# smps_v_1_1.net
KiCad netlist of a schematic drawn in EAGLE
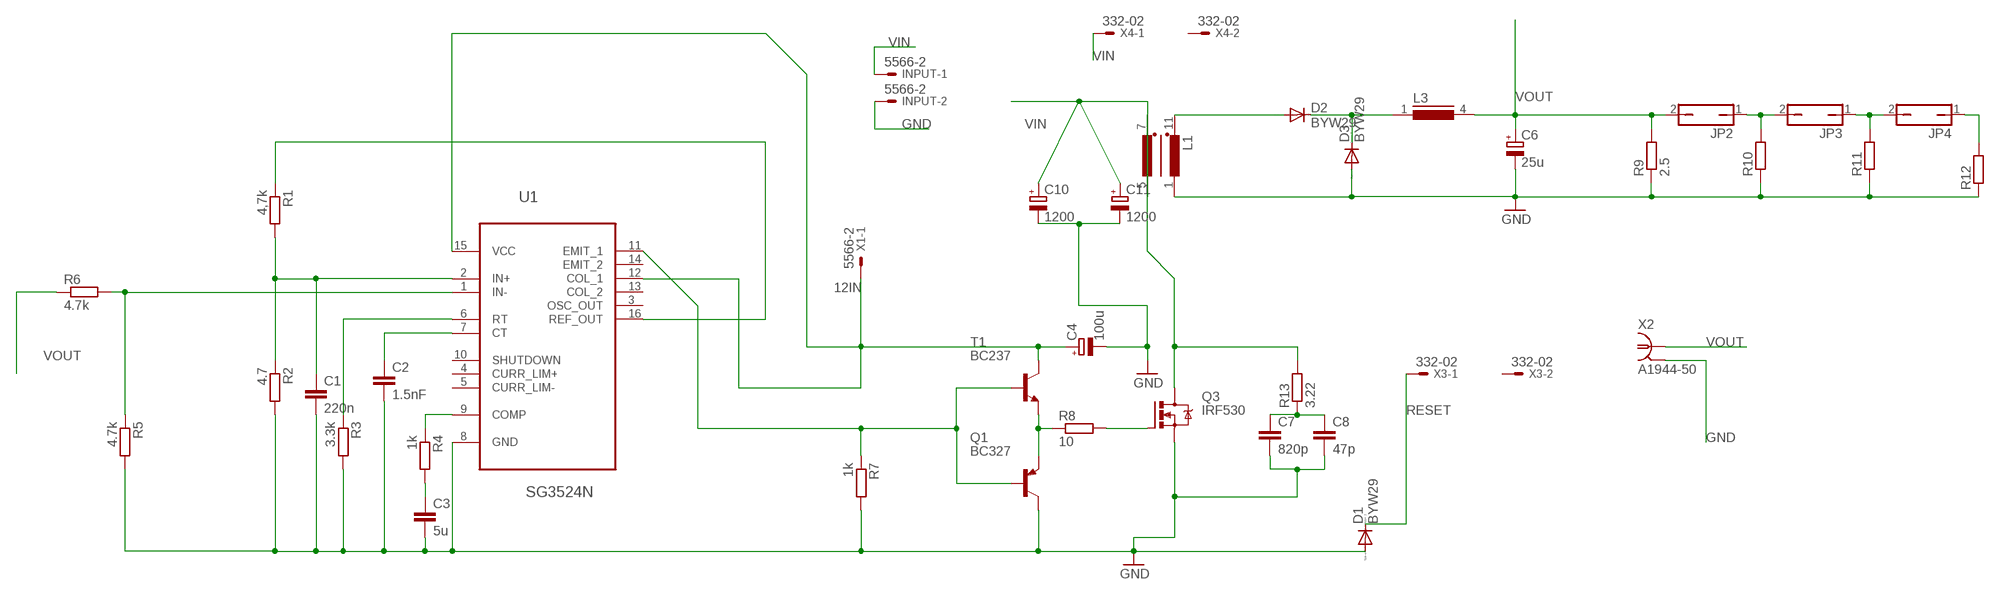
[diagram p0: schematic, sheet 1]

(export (version "E")
  (design (tool "Eeschema 10.0.6"))
  (components
    (comp (ref "C1")
      (value "220n")
      (footprint "eagle-import:C050-030X075")
      (libsource (lib "eagle-import") (part "resistor_C-EU050-030X075"))
    )
    (comp (ref "C2")
      (value "1.5nF")
      (footprint "eagle-import:C050-035X075")
      (libsource (lib "eagle-import") (part "C-EU050-035X075"))
    )
    (comp (ref "C3")
      (value "5u")
      (footprint "eagle-import:C050-035X075")
      (libsource (lib "eagle-import") (part "C-EU050-035X075"))
    )
    (comp (ref "C4")
      (value "100u")
      (footprint "eagle-import:E2-4")
      (libsource (lib "eagle-import") (part "CPOL-EUE2-4"))
    )
    (comp (ref "C6")
      (value "25u")
      (footprint "eagle-import:E2-4")
      (libsource (lib "eagle-import") (part "CPOL-EUE2-4"))
    )
    (comp (ref "C7")
      (value "820p")
      (footprint "eagle-import:C025-025X050")
      (libsource (lib "eagle-import") (part "C-EU025-025X050"))
    )
    (comp (ref "C8")
      (value "47p")
      (footprint "eagle-import:C025-025X050")
      (libsource (lib "eagle-import") (part "C-EU025-025X050"))
    )
    (comp (ref "C10")
      (value "1200")
      (footprint "eagle-import:E7,5-16")
      (libsource (lib "eagle-import") (part "CPOL-EUE7.5-16"))
    )
    (comp (ref "C11")
      (value "1200")
      (footprint "eagle-import:E7,5-16")
      (libsource (lib "eagle-import") (part "CPOL-EUE7.5-16"))
    )
    (comp (ref "D1")
      (value "BYW29")
      (footprint "eagle-import:DO220S")
      (libsource (lib "eagle-import") (part "BYW29"))
    )
    (comp (ref "D2")
      (value "BYW29")
      (footprint "eagle-import:DO220S")
      (libsource (lib "eagle-import") (part "BYW29"))
    )
    (comp (ref "D3")
      (value "BYW29")
      (footprint "eagle-import:DO220S")
      (libsource (lib "eagle-import") (part "BYW29"))
    )
    (comp (ref "INPUT")
      (value "5566-2")
      (footprint "eagle-import:5566-2")
      (libsource (lib "eagle-import") (part "5566-2"))
    )
    (comp (ref "JP2")
      (value "JP1Q")
      (footprint "eagle-import:JP1")
      (libsource (lib "eagle-import") (part "JP1Q"))
    )
    (comp (ref "JP3")
      (value "JP1Q")
      (footprint "eagle-import:JP1")
      (libsource (lib "eagle-import") (part "JP1Q"))
    )
    (comp (ref "JP4")
      (value "JP1Q")
      (footprint "eagle-import:JP1")
      (libsource (lib "eagle-import") (part "JP1Q"))
    )
    (comp (ref "L1")
      (value "RM6-2RM812")
      (footprint "eagle-import:RM8-12")
      (libsource (lib "eagle-import") (part "RM6-2RM812"))
    )
    (comp (ref "L3")
      (value "RM6NEWVARIANT")
      (footprint "eagle-import:RM7-8")
      (libsource (lib "eagle-import") (part "RM6NEWVARIANT"))
    )
    (comp (ref "Q1")
      (value "BC327")
      (footprint "eagle-import:TO92")
      (libsource (lib "eagle-import") (part "BC327"))
    )
    (comp (ref "Q3")
      (value "IRF530")
      (footprint "eagle-import:TO220BV")
      (libsource (lib "eagle-import") (part "IRF530"))
    )
    (comp (ref "R1")
      (value "4,7k")
      (footprint "eagle-import:0204_7")
      (libsource (lib "eagle-import") (part "resistor_R-EU_0204/7"))
    )
    (comp (ref "R2")
      (value "4.7")
      (footprint "eagle-import:0204_7")
      (libsource (lib "eagle-import") (part "resistor_R-EU_0204/7"))
    )
    (comp (ref "R3")
      (value "3.3k")
      (footprint "eagle-import:0204_7")
      (libsource (lib "eagle-import") (part "resistor_R-EU_0204/7"))
    )
    (comp (ref "R4")
      (value "1k")
      (footprint "eagle-import:0204_7")
      (libsource (lib "eagle-import") (part "resistor_R-EU_0204/7"))
    )
    (comp (ref "R5")
      (value "4.7k")
      (footprint "eagle-import:0204_7")
      (libsource (lib "eagle-import") (part "resistor_R-EU_0204/7"))
    )
    (comp (ref "R6")
      (value "4.7k")
      (footprint "eagle-import:0204_7")
      (libsource (lib "eagle-import") (part "resistor_R-EU_0204/7"))
    )
    (comp (ref "R7")
      (value "1k")
      (footprint "eagle-import:0204_7")
      (libsource (lib "eagle-import") (part "resistor_R-EU_0204/7"))
    )
    (comp (ref "R8")
      (value "10")
      (footprint "eagle-import:0204_7")
      (libsource (lib "eagle-import") (part "resistor_R-EU_0204/7"))
    )
    (comp (ref "R9")
      (value "2.5")
      (footprint "eagle-import:0617V")
      (libsource (lib "eagle-import") (part "R-EU_0617/5V"))
    )
    (comp (ref "R10")
      (value "R-EU_0617/5V")
      (footprint "eagle-import:0617V")
      (libsource (lib "eagle-import") (part "R-EU_0617/5V"))
    )
    (comp (ref "R11")
      (value "R-EU_0617/5V")
      (footprint "eagle-import:0617V")
      (libsource (lib "eagle-import") (part "R-EU_0617/5V"))
    )
    (comp (ref "R12")
      (value "R-EU_0617/5V")
      (footprint "eagle-import:0617V")
      (libsource (lib "eagle-import") (part "R-EU_0617/5V"))
    )
    (comp (ref "R13")
      (value "3.22")
      (footprint "eagle-import:0204V")
      (libsource (lib "eagle-import") (part "R-EU_0204/2V"))
    )
    (comp (ref "T1")
      (value "BC237")
      (footprint "eagle-import:TO92")
      (libsource (lib "eagle-import") (part "BC237"))
    )
    (comp (ref "U1")
      (value "SG3524N")
      (footprint "eagle-import:DIP254P762X508-16")
      (libsource (lib "eagle-import") (part "SG3524N"))
    )
    (comp (ref "X1")
      (value "5566-2")
      (footprint "eagle-import:5566-2")
      (libsource (lib "eagle-import") (part "5566-2"))
    )
    (comp (ref "X2")
      (value "A1944-50")
      (footprint "eagle-import:A1944")
      (libsource (lib "eagle-import") (part "A1944-50"))
    )
    (comp (ref "X3")
      (value "332-02")
      (footprint "eagle-import:332-02")
      (libsource (lib "eagle-import") (part "332-02"))
    )
    (comp (ref "X4")
      (value "332-02")
      (footprint "eagle-import:332-02")
      (libsource (lib "eagle-import") (part "332-02"))
    )
  )
  (nets
    (net (code "1") (name "/12IN") (class "Default")
      (node (ref "C4") (pin "+") (pinfunction "+_+") (pintype "passive"))
      (node (ref "T1") (pin "3") (pinfunction "C_3") (pintype "passive"))
      (node (ref "U1") (pin "12") (pinfunction "COL_1_12") (pintype "passive"))
      (node (ref "U1") (pin "15") (pinfunction "VCC_15") (pintype "power_in"))
      (node (ref "X1") (pin "1") (pinfunction "S_1") (pintype "passive"))
    )
    (net (code "2") (name "/RESET") (class "Default")
      (node (ref "D1") (pin "C") (pinfunction "C_C") (pintype "passive"))
      (node (ref "X3") (pin "1") (pinfunction "S_1") (pintype "passive"))
    )
    (net (code "3") (name "/VIN") (class "Default")
      (node (ref "C10") (pin "+") (pinfunction "+_+") (pintype "passive"))
      (node (ref "C11") (pin "+") (pinfunction "+_+") (pintype "passive"))
      (node (ref "INPUT") (pin "1") (pinfunction "S_1") (pintype "passive"))
      (node (ref "L1") (pin "5") (pinfunction "W2E_5") (pintype "passive"))
      (node (ref "X4") (pin "1") (pinfunction "S_1") (pintype "passive"))
    )
    (net (code "4") (name "/VOUT") (class "Default")
      (node (ref "C6") (pin "+") (pinfunction "+_+") (pintype "passive"))
      (node (ref "JP2") (pin "2") (pinfunction "2_2") (pintype "passive"))
      (node (ref "L3") (pin "4") (pinfunction "2_4") (pintype "passive"))
      (node (ref "R6") (pin "1") (pinfunction "1_1") (pintype "passive"))
      (node (ref "R9") (pin "2") (pinfunction "2_2") (pintype "passive"))
      (node (ref "X2") (pin "1") (pinfunction "1_1") (pintype "passive"))
    )
    (net (code "5") (name "GND") (class "Default")
      (node (ref "C1") (pin "2") (pinfunction "2_2") (pintype "passive"))
      (node (ref "C10") (pin "-") (pinfunction "-_-") (pintype "passive"))
      (node (ref "C11") (pin "-") (pinfunction "-_-") (pintype "passive"))
      (node (ref "C2") (pin "2") (pinfunction "2_2") (pintype "passive"))
      (node (ref "C3") (pin "2") (pinfunction "2_2") (pintype "passive"))
      (node (ref "C4") (pin "-") (pinfunction "-_-") (pintype "passive"))
      (node (ref "C6") (pin "-") (pinfunction "-_-") (pintype "passive"))
      (node (ref "C7") (pin "2") (pinfunction "2_2") (pintype "passive"))
      (node (ref "C8") (pin "2") (pinfunction "2_2") (pintype "passive"))
      (node (ref "D1") (pin "A") (pinfunction "A_A") (pintype "passive"))
      (node (ref "D3") (pin "A") (pinfunction "A_A") (pintype "passive"))
      (node (ref "INPUT") (pin "2") (pinfunction "S_2") (pintype "passive"))
      (node (ref "L1") (pin "1") (pinfunction "W1E_1") (pintype "passive"))
      (node (ref "Q1") (pin "3") (pinfunction "C_3") (pintype "passive"))
      (node (ref "Q3") (pin "S") (pinfunction "S_S") (pintype "passive"))
      (node (ref "R10") (pin "1") (pinfunction "1_1") (pintype "passive"))
      (node (ref "R11") (pin "1") (pinfunction "1_1") (pintype "passive"))
      (node (ref "R12") (pin "1") (pinfunction "1_1") (pintype "passive"))
      (node (ref "R2") (pin "2") (pinfunction "2_2") (pintype "passive"))
      (node (ref "R3") (pin "2") (pinfunction "2_2") (pintype "passive"))
      (node (ref "R5") (pin "2") (pinfunction "2_2") (pintype "passive"))
      (node (ref "R7") (pin "2") (pinfunction "2_2") (pintype "passive"))
      (node (ref "R9") (pin "1") (pinfunction "1_1") (pintype "passive"))
      (node (ref "U1") (pin "8") (pinfunction "GND_8") (pintype "passive"))
      (node (ref "X2") (pin "2") (pinfunction "2_2") (pintype "passive"))
      (node (ref "X2") (pin "3") (pinfunction "2_3") (pintype "passive"))
      (node (ref "X2") (pin "4") (pinfunction "2_4") (pintype "passive"))
      (node (ref "X2") (pin "5") (pinfunction "2_5") (pintype "passive"))
    )
    (net (code "6") (name "Net-(C3-Pad1)") (class "Default")
      (node (ref "C3") (pin "1") (pinfunction "1_1") (pintype "passive"))
      (node (ref "R4") (pin "2") (pinfunction "2_2") (pintype "passive"))
    )
    (net (code "7") (name "Net-(C7-Pad1)") (class "Default")
      (node (ref "C7") (pin "1") (pinfunction "1_1") (pintype "passive"))
      (node (ref "C8") (pin "1") (pinfunction "1_1") (pintype "passive"))
      (node (ref "R13") (pin "1") (pinfunction "1_1") (pintype "passive"))
    )
    (net (code "8") (name "Net-(D2-PadC)") (class "Default")
      (node (ref "D2") (pin "C") (pinfunction "C_C") (pintype "passive"))
      (node (ref "D3") (pin "C") (pinfunction "C_C") (pintype "passive"))
      (node (ref "L3") (pin "1") (pinfunction "1_1") (pintype "passive"))
    )
    (net (code "9") (name "Net-(JP2-Pad1)") (class "Default")
      (node (ref "JP2") (pin "1") (pinfunction "1_1") (pintype "passive"))
      (node (ref "JP3") (pin "2") (pinfunction "2_2") (pintype "passive"))
      (node (ref "R10") (pin "2") (pinfunction "2_2") (pintype "passive"))
    )
    (net (code "10") (name "Net-(JP3-Pad1)") (class "Default")
      (node (ref "JP3") (pin "1") (pinfunction "1_1") (pintype "passive"))
      (node (ref "JP4") (pin "2") (pinfunction "2_2") (pintype "passive"))
      (node (ref "R11") (pin "2") (pinfunction "2_2") (pintype "passive"))
    )
    (net (code "11") (name "Net-(JP4-Pad1)") (class "Default")
      (node (ref "JP4") (pin "1") (pinfunction "1_1") (pintype "passive"))
      (node (ref "R12") (pin "2") (pinfunction "2_2") (pintype "passive"))
    )
    (net (code "12") (name "Net-(L1-W1A)") (class "Default")
      (node (ref "D2") (pin "A") (pinfunction "A_A") (pintype "passive"))
      (node (ref "L1") (pin "11") (pinfunction "W1A_11") (pintype "passive"))
    )
    (net (code "13") (name "Net-(L1-W2A)") (class "Default")
      (node (ref "L1") (pin "7") (pinfunction "W2A_7") (pintype "passive"))
      (node (ref "Q3") (pin "D") (pinfunction "D_D") (pintype "passive"))
      (node (ref "R13") (pin "2") (pinfunction "2_2") (pintype "passive"))
    )
    (net (code "14") (name "Net-(Q1-B)") (class "Default")
      (node (ref "Q1") (pin "2") (pinfunction "B_2") (pintype "passive"))
      (node (ref "R7") (pin "1") (pinfunction "1_1") (pintype "passive"))
      (node (ref "T1") (pin "2") (pinfunction "B_2") (pintype "passive"))
      (node (ref "U1") (pin "11") (pinfunction "EMIT_1_11") (pintype "passive"))
    )
    (net (code "15") (name "Net-(Q1-E)") (class "Default")
      (node (ref "Q1") (pin "1") (pinfunction "E_1") (pintype "passive"))
      (node (ref "R8") (pin "1") (pinfunction "1_1") (pintype "passive"))
      (node (ref "T1") (pin "1") (pinfunction "E_1") (pintype "passive"))
    )
    (net (code "16") (name "Net-(Q3-PadG)") (class "Default")
      (node (ref "Q3") (pin "G") (pinfunction "G_G") (pintype "passive"))
      (node (ref "R8") (pin "2") (pinfunction "2_2") (pintype "passive"))
    )
    (net (code "17") (name "Net-(U1-COMP)") (class "Default")
      (node (ref "R4") (pin "1") (pinfunction "1_1") (pintype "passive"))
      (node (ref "U1") (pin "9") (pinfunction "COMP_9") (pintype "passive"))
    )
    (net (code "18") (name "Net-(U1-CT)") (class "Default")
      (node (ref "C2") (pin "1") (pinfunction "1_1") (pintype "passive"))
      (node (ref "U1") (pin "7") (pinfunction "CT_7") (pintype "input"))
    )
    (net (code "19") (name "Net-(U1-IN+)") (class "Default")
      (node (ref "C1") (pin "1") (pinfunction "1_1") (pintype "passive"))
      (node (ref "R1") (pin "2") (pinfunction "2_2") (pintype "passive"))
      (node (ref "R2") (pin "1") (pinfunction "1_1") (pintype "passive"))
      (node (ref "U1") (pin "2") (pinfunction "IN+_2") (pintype "input"))
    )
    (net (code "20") (name "Net-(U1-IN-)") (class "Default")
      (node (ref "R5") (pin "1") (pinfunction "1_1") (pintype "passive"))
      (node (ref "R6") (pin "2") (pinfunction "2_2") (pintype "passive"))
      (node (ref "U1") (pin "1") (pinfunction "IN-_1") (pintype "input"))
    )
    (net (code "21") (name "Net-(U1-REF_OUT)") (class "Default")
      (node (ref "R1") (pin "1") (pinfunction "1_1") (pintype "passive"))
      (node (ref "U1") (pin "16") (pinfunction "REF_OUT_16") (pintype "output"))
    )
    (net (code "22") (name "Net-(U1-RT)") (class "Default")
      (node (ref "R3") (pin "1") (pinfunction "1_1") (pintype "passive"))
      (node (ref "U1") (pin "6") (pinfunction "RT_6") (pintype "input"))
    )
    (net (code "23") (name "unconnected-(U1-COL_2-Pad13)") (class "Default")
      (node (ref "U1") (pin "13") (pinfunction "COL_2_13") (pintype "passive"))
    )
    (net (code "24") (name "unconnected-(U1-CURR_LIM+-Pad4)") (class "Default")
      (node (ref "U1") (pin "4") (pinfunction "CURR_LIM+_4") (pintype "input"))
    )
    (net (code "25") (name "unconnected-(U1-CURR_LIM--Pad5)") (class "Default")
      (node (ref "U1") (pin "5") (pinfunction "CURR_LIM-_5") (pintype "input"))
    )
    (net (code "26") (name "unconnected-(U1-EMIT_2-Pad14)") (class "Default")
      (node (ref "U1") (pin "14") (pinfunction "EMIT_2_14") (pintype "passive"))
    )
    (net (code "27") (name "unconnected-(U1-OSC_OUT-Pad3)") (class "Default")
      (node (ref "U1") (pin "3") (pinfunction "OSC_OUT_3") (pintype "output"))
    )
    (net (code "28") (name "unconnected-(U1-SHUTDOWN-Pad10)") (class "Default")
      (node (ref "U1") (pin "10") (pinfunction "SHUTDOWN_10") (pintype "input"))
    )
    (net (code "29") (name "unconnected-(X3B-S-Pad2)") (class "Default")
      (node (ref "X3") (pin "2") (pinfunction "S_2") (pintype "passive"))
    )
    (net (code "30") (name "unconnected-(X4B-S-Pad2)") (class "Default")
      (node (ref "X4") (pin "2") (pinfunction "S_2") (pintype "passive"))
    )
  )
)
